# demulplx.net
KiCad netlist of a schematic drawn in EAGLE
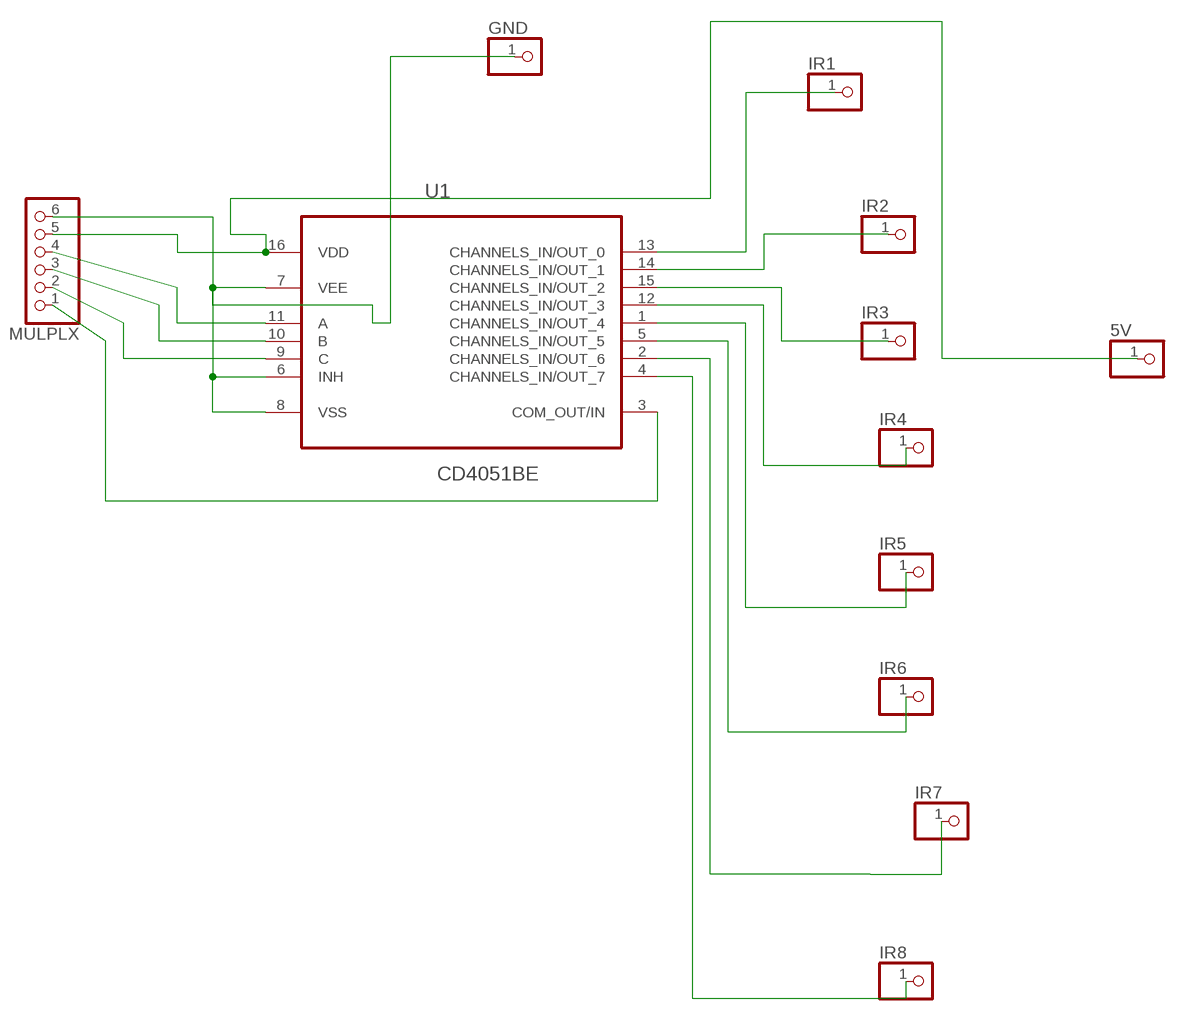
[diagram p0: schematic, sheet 1]

(export (version "E")
  (design (tool "Eeschema 10.0.6"))
  (components
    (comp (ref "5V")
      (value "PINHD-1X01_2.54")
      (footprint "eagle-import:1X01")
      (libsource (lib "eagle-import") (part "PINHD-1X01_2.54"))
    )
    (comp (ref "GND")
      (value "PINHD-1X01_2.54")
      (footprint "eagle-import:1X01")
      (libsource (lib "eagle-import") (part "PINHD-1X01_2.54"))
    )
    (comp (ref "IR1")
      (value "PINHD-1X01_2.54")
      (footprint "eagle-import:1X01")
      (libsource (lib "eagle-import") (part "PINHD-1X01_2.54"))
    )
    (comp (ref "IR2")
      (value "PINHD-1X01_2.54")
      (footprint "eagle-import:1X01")
      (libsource (lib "eagle-import") (part "PINHD-1X01_2.54"))
    )
    (comp (ref "IR3")
      (value "PINHD-1X01_2.54")
      (footprint "eagle-import:1X01")
      (libsource (lib "eagle-import") (part "PINHD-1X01_2.54"))
    )
    (comp (ref "IR4")
      (value "PINHD-1X01_2.54")
      (footprint "eagle-import:1X01")
      (libsource (lib "eagle-import") (part "PINHD-1X01_2.54"))
    )
    (comp (ref "IR5")
      (value "PINHD-1X01_2.54")
      (footprint "eagle-import:1X01")
      (libsource (lib "eagle-import") (part "PINHD-1X01_2.54"))
    )
    (comp (ref "IR6")
      (value "PINHD-1X01_2.54")
      (footprint "eagle-import:1X01")
      (libsource (lib "eagle-import") (part "PINHD-1X01_2.54"))
    )
    (comp (ref "IR7")
      (value "PINHD-1X01_2.54")
      (footprint "eagle-import:1X01")
      (libsource (lib "eagle-import") (part "PINHD-1X01_2.54"))
    )
    (comp (ref "IR8")
      (value "PINHD-1X01_2.54")
      (footprint "eagle-import:1X01")
      (libsource (lib "eagle-import") (part "PINHD-1X01_2.54"))
    )
    (comp (ref "MULPLX")
      (value "PINHD-1X06_2.54-S")
      (footprint "eagle-import:1X06-S")
      (libsource (lib "eagle-import") (part "PINHD-1X06_2.54-S"))
    )
    (comp (ref "U1")
      (value "CD4051BE")
      (footprint "eagle-import:DIP254P762X508-16")
      (libsource (lib "eagle-import") (part "CD4051BE"))
    )
  )
  (nets
    (net (code "1") (name "Net-(U1-A)") (class "Default")
      (node (ref "MULPLX") (pin "4") (pinfunction "4_4") (pintype "passive"))
      (node (ref "U1") (pin "11") (pinfunction "A_11") (pintype "input"))
    )
    (net (code "2") (name "Net-(U1-B)") (class "Default")
      (node (ref "MULPLX") (pin "3") (pinfunction "3_3") (pintype "passive"))
      (node (ref "U1") (pin "10") (pinfunction "B_10") (pintype "input"))
    )
    (net (code "3") (name "Net-(U1-C)") (class "Default")
      (node (ref "MULPLX") (pin "2") (pinfunction "2_2") (pintype "passive"))
      (node (ref "U1") (pin "9") (pinfunction "C_9") (pintype "input"))
    )
    (net (code "4") (name "Net-(U1-CHANNELS_IN{slash}OUT_0)") (class "Default")
      (node (ref "IR1") (pin "1") (pinfunction "1_1") (pintype "passive"))
      (node (ref "U1") (pin "13") (pinfunction "CHANNELS_IN/OUT_0_13") (pintype "bidirectional"))
    )
    (net (code "5") (name "Net-(U1-CHANNELS_IN{slash}OUT_1)") (class "Default")
      (node (ref "IR2") (pin "1") (pinfunction "1_1") (pintype "passive"))
      (node (ref "U1") (pin "14") (pinfunction "CHANNELS_IN/OUT_1_14") (pintype "bidirectional"))
    )
    (net (code "6") (name "Net-(U1-CHANNELS_IN{slash}OUT_2)") (class "Default")
      (node (ref "IR3") (pin "1") (pinfunction "1_1") (pintype "passive"))
      (node (ref "U1") (pin "15") (pinfunction "CHANNELS_IN/OUT_2_15") (pintype "bidirectional"))
    )
    (net (code "7") (name "Net-(U1-CHANNELS_IN{slash}OUT_3)") (class "Default")
      (node (ref "IR4") (pin "1") (pinfunction "1_1") (pintype "passive"))
      (node (ref "U1") (pin "12") (pinfunction "CHANNELS_IN/OUT_3_12") (pintype "bidirectional"))
    )
    (net (code "8") (name "Net-(U1-CHANNELS_IN{slash}OUT_4)") (class "Default")
      (node (ref "IR5") (pin "1") (pinfunction "1_1") (pintype "passive"))
      (node (ref "U1") (pin "1") (pinfunction "CHANNELS_IN/OUT_4_1") (pintype "bidirectional"))
    )
    (net (code "9") (name "Net-(U1-CHANNELS_IN{slash}OUT_5)") (class "Default")
      (node (ref "IR6") (pin "1") (pinfunction "1_1") (pintype "passive"))
      (node (ref "U1") (pin "5") (pinfunction "CHANNELS_IN/OUT_5_5") (pintype "bidirectional"))
    )
    (net (code "10") (name "Net-(U1-CHANNELS_IN{slash}OUT_6)") (class "Default")
      (node (ref "IR7") (pin "1") (pinfunction "1_1") (pintype "passive"))
      (node (ref "U1") (pin "2") (pinfunction "CHANNELS_IN/OUT_6_2") (pintype "bidirectional"))
    )
    (net (code "11") (name "Net-(U1-CHANNELS_IN{slash}OUT_7)") (class "Default")
      (node (ref "IR8") (pin "1") (pinfunction "1_1") (pintype "passive"))
      (node (ref "U1") (pin "4") (pinfunction "CHANNELS_IN/OUT_7_4") (pintype "bidirectional"))
    )
    (net (code "12") (name "Net-(U1-COM_OUT{slash}IN)") (class "Default")
      (node (ref "MULPLX") (pin "1") (pinfunction "1_1") (pintype "passive"))
      (node (ref "U1") (pin "3") (pinfunction "COM_OUT/IN_3") (pintype "bidirectional"))
    )
    (net (code "13") (name "Net-(U1-INH)") (class "Default")
      (node (ref "GND") (pin "1") (pinfunction "1_1") (pintype "passive"))
      (node (ref "MULPLX") (pin "6") (pinfunction "6_6") (pintype "passive"))
      (node (ref "U1") (pin "6") (pinfunction "INH_6") (pintype "input"))
      (node (ref "U1") (pin "7") (pinfunction "VEE_7") (pintype "power_in"))
      (node (ref "U1") (pin "8") (pinfunction "VSS_8") (pintype "power_in"))
    )
    (net (code "14") (name "Net-(U1-VDD)") (class "Default")
      (node (ref "5V") (pin "1") (pinfunction "1_1") (pintype "passive"))
      (node (ref "MULPLX") (pin "5") (pinfunction "5_5") (pintype "passive"))
      (node (ref "U1") (pin "16") (pinfunction "VDD_16") (pintype "power_in"))
    )
  )
)
